# USB_to_UART0_interface.net
KiCad netlist of a schematic drawn in Altium Designer
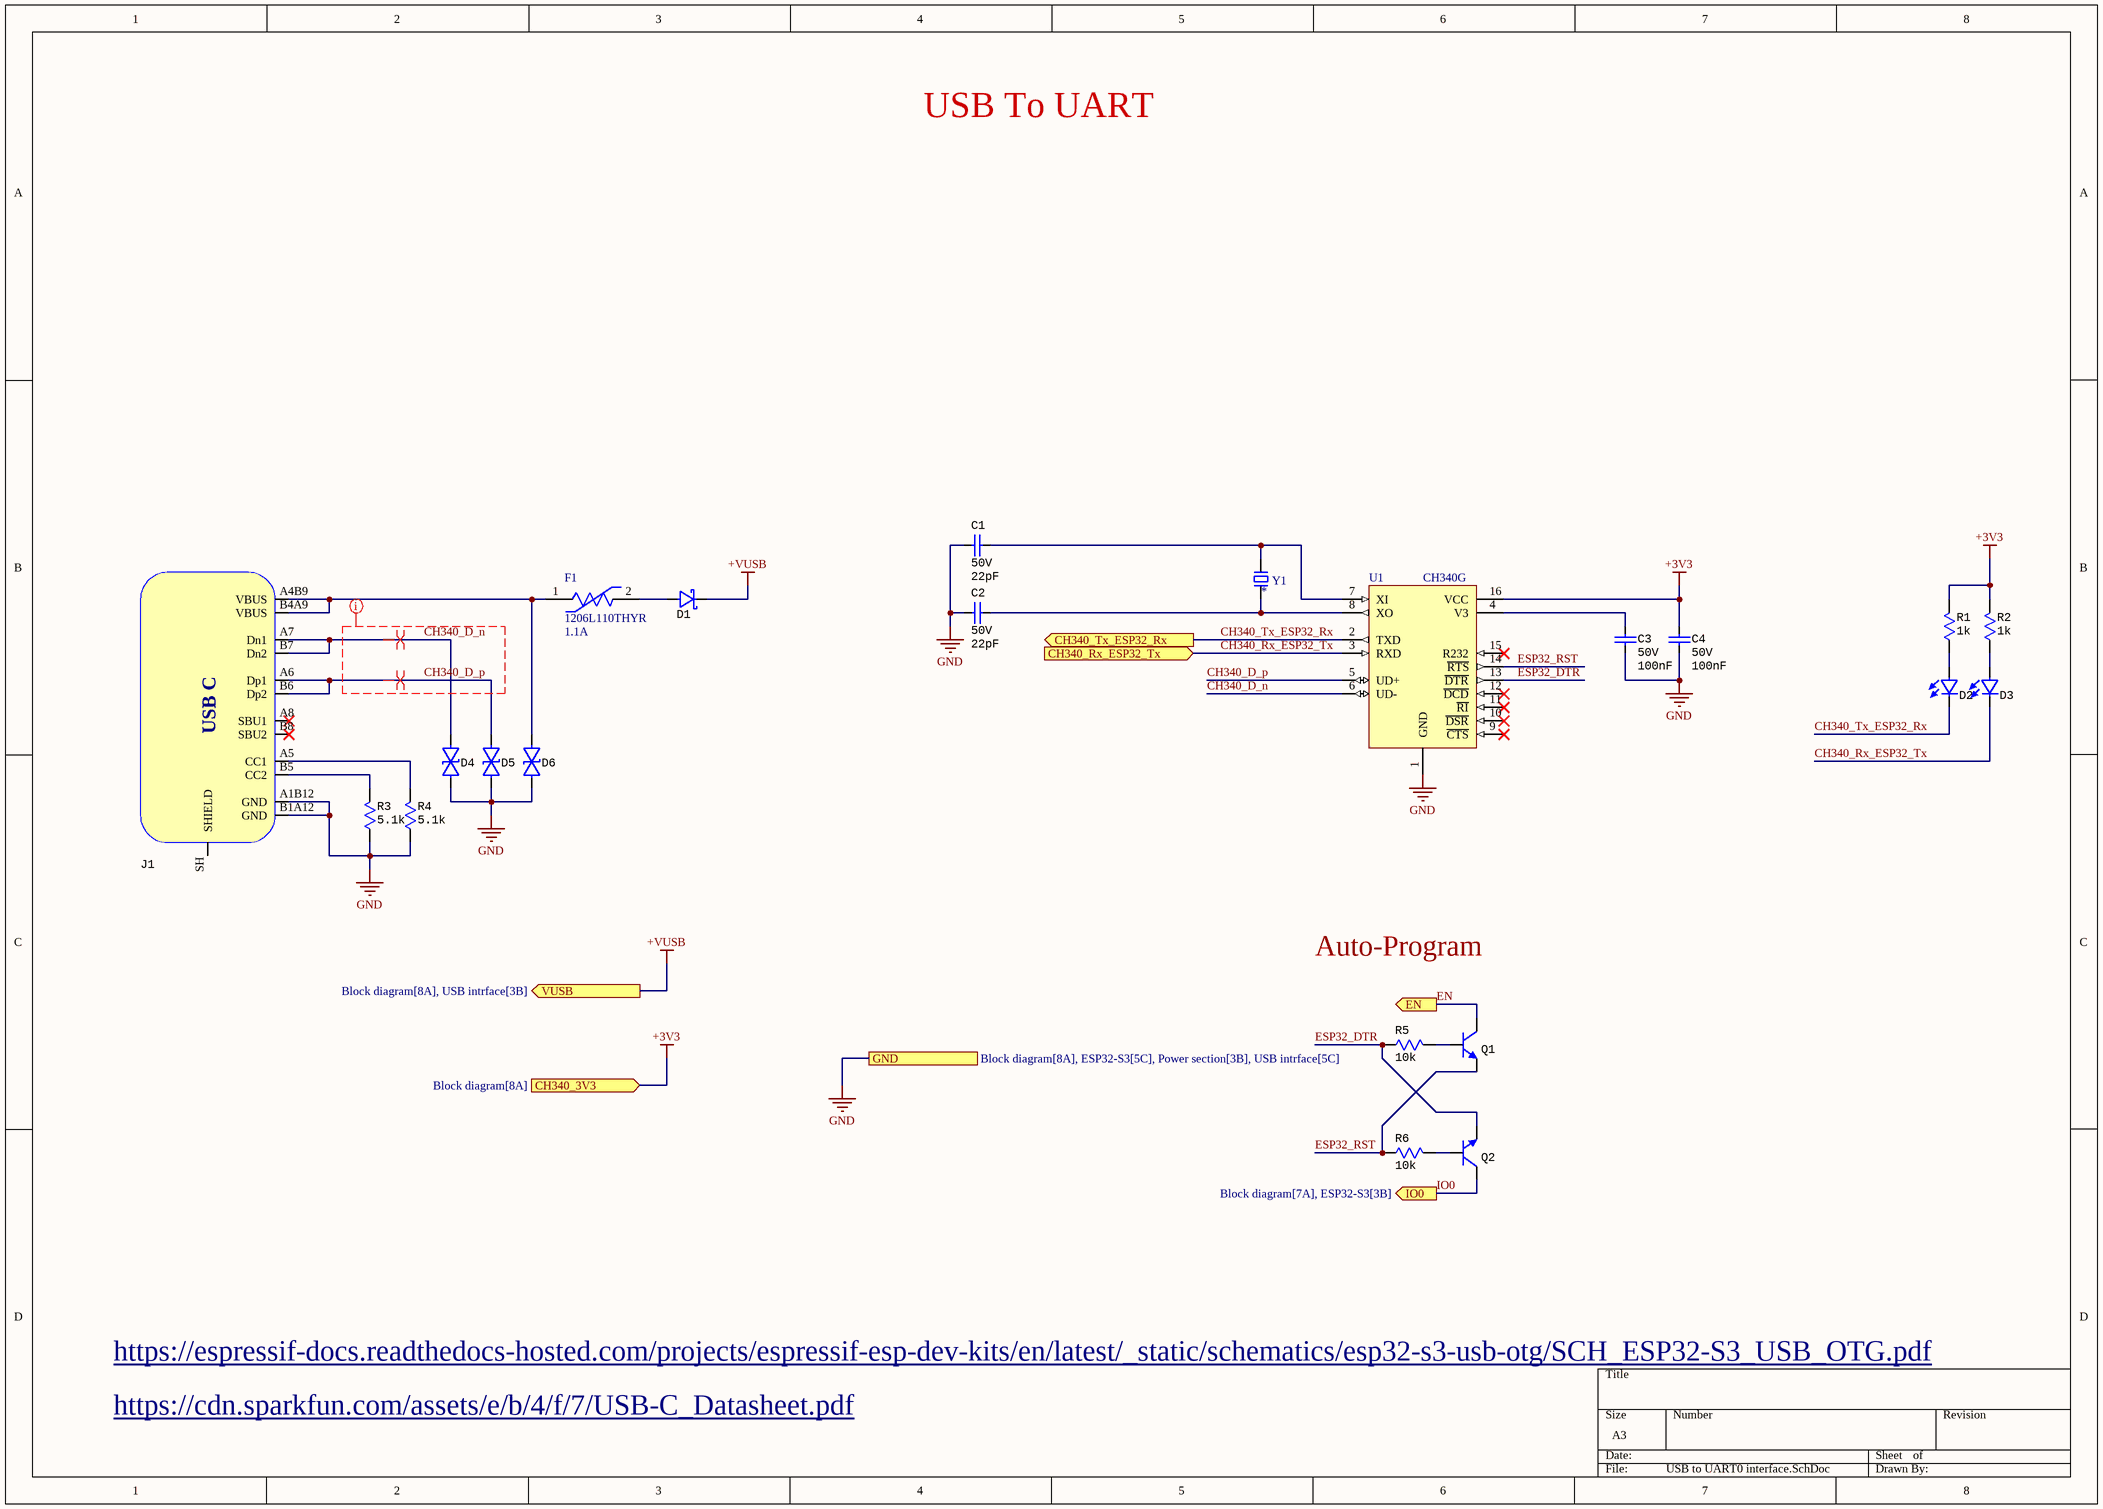
[diagram p0: USB to UART0 interface.SchDoc]

(export (version "E")
  (design (tool "Eeschema 10.0.6"))
  (components
    (comp (ref "C1")
      (value "22pF")
      (footprint "CAP Ceramic SMD 0603")
      (description "CAP CER 22PF 50V C0G/NP0 0603")
      (fields
        (field (name "MANUFACTURER") "Samsung")
        (field (name "MANUFACTURER PART NUMBER") "CL10C220JB81PNC")
        (field (name "VOLTAGE") "50V")
      )
      (libsource (lib "Passive") (part "CAP 0603 22pF 50V"))
    )
    (comp (ref "C2")
      (value "22pF")
      (footprint "CAP Ceramic SMD 0603")
      (description "CAP CER 22PF 50V C0G/NP0 0603")
      (fields
        (field (name "MANUFACTURER") "Samsung")
        (field (name "MANUFACTURER PART NUMBER") "CL10C220JB81PNC")
        (field (name "VOLTAGE") "50V")
      )
      (libsource (lib "Passive") (part "CAP 0603 22pF 50V"))
    )
    (comp (ref "C3")
      (value "100nF")
      (footprint "CAP Ceramic SMD 0603")
      (description "Multilayer Ceramic Capacitors MLCC Surface Mount 0603 0.1uF 50 Volts X7R 10%")
      (fields
        (field (name "MANUFACTURER") "Murata")
        (field (name "MANUFACTURER PART NUMBER") "GRM188R71H104KA93D")
        (field (name "VOLTAGE") "50V")
      )
      (libsource (lib "Passive") (part "CAP 0603 100nF 50V"))
    )
    (comp (ref "C4")
      (value "100nF")
      (footprint "CAP Ceramic SMD 0603")
      (description "Multilayer Ceramic Capacitors MLCC Surface Mount 0603 0.1uF 50 Volts X7R 10%")
      (fields
        (field (name "MANUFACTURER") "Murata")
        (field (name "MANUFACTURER PART NUMBER") "GRM188R71H104KA93D")
        (field (name "VOLTAGE") "50V")
      )
      (libsource (lib "Passive") (part "CAP 0603 100nF 50V"))
    )
    (comp (ref "D1")
      (value "~")
      (footprint "Diode Single SMD SOD123")
      (description "40V 600mV@1A 1A SOD-123 Schottky Barrier Diodes (SBD) ROHS")
      (fields (field (name "MANUFACTURER") "MCC") (field (name "MANUFACTURER PART NUMBER") "B5819W-TP"))
      (libsource (lib "diode") (part "B5819W"))
    )
    (comp (ref "D2")
      (value "~")
      (footprint "LED SMD 0805G")
      (fields
        (field (name "MANUFACTURER") "FOSHAN Nationstar Optoelectronics")
        (field (name "MANUFACTURER PART NUMBER") "NCD0805G1")
      )
      (libsource (lib "diode") (part "LED 0805 Emerald"))
    )
    (comp (ref "D3")
      (value "~")
      (footprint "LED SMD 0805G")
      (fields
        (field (name "MANUFACTURER") "FOSHAN Nationstar Optoelectronics")
        (field (name "MANUFACTURER PART NUMBER") "NCD0805G1")
      )
      (libsource (lib "diode") (part "LED 0805 Emerald"))
    )
    (comp (ref "D4")
      (value "~")
      (footprint "Diode Single SMD SOD523")
      (description "Bi-Directional 9.4A 5V 18.6V 5.6V SOD-523 ESD Protection Devices ROHS")
      (fields
        (field (name "MANUFACTURER") "UMW(Youtai Semiconductor)")
        (field (name "MANUFACTURER PART NUMBER") "LESD5D5.0CT1G")
      )
      (libsource (lib "diode") (part "LESD5D5.0CT1G"))
    )
    (comp (ref "D5")
      (value "~")
      (footprint "Diode Single SMD SOD523")
      (description "Bi-Directional 9.4A 5V 18.6V 5.6V SOD-523 ESD Protection Devices ROHS")
      (fields
        (field (name "MANUFACTURER") "UMW(Youtai Semiconductor)")
        (field (name "MANUFACTURER PART NUMBER") "LESD5D5.0CT1G")
      )
      (libsource (lib "diode") (part "LESD5D5.0CT1G"))
    )
    (comp (ref "D6")
      (value "~")
      (footprint "Diode Single SMD SOD523")
      (description "Bi-Directional 9.4A 5V 18.6V 5.6V SOD-523 ESD Protection Devices ROHS")
      (fields
        (field (name "MANUFACTURER") "UMW(Youtai Semiconductor)")
        (field (name "MANUFACTURER PART NUMBER") "LESD5D5.0CT1G")
      )
      (libsource (lib "diode") (part "LESD5D5.0CT1G"))
    )
    (comp (ref "F1")
      (value "1206L110THYR")
      (footprint "FUSE-1206")
      (description "PTC RESET FUSE 8V 1.1A 1206")
      (fields
        (field (name "MANUFACTURER") "Littelfuse")
        (field (name "OCTOPART") "https://octopart.com/1206l110thyr-littelfuse-11800142")
        (field (name "HOLD CURRENT") "1.1A")
      )
      (libsource (lib "Fuse") (part "1206L110THYR"))
    )
    (comp (ref "J1")
      (value "Connector_USB_Type_C_12Pin")
      (footprint "USB-C-31-M-12 (12PIN)")
      (description "Korean Hroparts Elec\r\nUSB-Type-C\r\nNum of contacts 16\r\nSurface Mount")
      (fields
        (field (name "MANUFACTURER") "Korean Hroparts")
        (field (name "MANUFACTURERPARTNUMBER") "TYPE-C-31-M-12")
      )
      (libsource (lib "USB connectors") (part "Connector_USB_Type_C_12Pin"))
    )
    (comp (ref "Q1")
      (value "~")
      (footprint "SOT23")
      (description "NPN Ic=500mA Vceo=45V hfe=100~250 P=225mW SOT-23")
      (fields
        (field (name "MANUFACTURER") "ON Semiconductor")
        (field (name "MANUFACTURER PART NUMBER") "BC817-16LT1G")
      )
      (libsource (lib "Miscellaneous Transistor") (part "BC817"))
    )
    (comp (ref "Q2")
      (value "~")
      (footprint "SOT23")
      (description "NPN Ic=500mA Vceo=45V hfe=100~250 P=225mW SOT-23")
      (fields
        (field (name "MANUFACTURER") "ON Semiconductor")
        (field (name "MANUFACTURER PART NUMBER") "BC817-16LT1G")
      )
      (libsource (lib "Miscellaneous Transistor") (part "BC817"))
    )
    (comp (ref "R1")
      (value "1k")
      (footprint "RES SMD 0603")
      (description "Res Thick Film 0603 1K Ohm 1% 1/10W ±100ppm/°C Molded SMD Punched Carrier T/R")
      (fields
        (field (name "MANUFACTURER") "Panasonic")
        (field (name "MANUFACTURER PART NUMBER") "ERJ3EKF1001V")
      )
      (libsource (lib "Passive") (part "RES 0603 1k 1%"))
    )
    (comp (ref "R2")
      (value "1k")
      (footprint "RES SMD 0603")
      (description "Res Thick Film 0603 1K Ohm 1% 1/10W ±100ppm/°C Molded SMD Punched Carrier T/R")
      (fields
        (field (name "MANUFACTURER") "Panasonic")
        (field (name "MANUFACTURER PART NUMBER") "ERJ3EKF1001V")
      )
      (libsource (lib "Passive") (part "RES 0603 1k 1%"))
    )
    (comp (ref "R3")
      (value "5.1k")
      (footprint "RES SMD 0603")
      (description "Res Thick Film 0603 5.1K Ohm 1% 1/10W ±100ppm/°C Molded SMD SMD Paper T/R")
      (fields
        (field (name "MANUFACTURER") "Vishay")
        (field (name "MANUFACTURER PART NUMBER") "CRCW06035K10FKEA")
      )
      (libsource (lib "Passive") (part "RES 0603 5.1k 1%"))
    )
    (comp (ref "R4")
      (value "5.1k")
      (footprint "RES SMD 0603")
      (description "Res Thick Film 0603 5.1K Ohm 1% 1/10W ±100ppm/°C Molded SMD SMD Paper T/R")
      (fields
        (field (name "MANUFACTURER") "Vishay")
        (field (name "MANUFACTURER PART NUMBER") "CRCW06035K10FKEA")
      )
      (libsource (lib "Passive") (part "RES 0603 5.1k 1%"))
    )
    (comp (ref "R5")
      (value "10k")
      (footprint "RES SMD 0603")
      (description "Res Thick Film 0603 10K Ohm 1% 1/10W ±100ppm/°C Molded SMD Punched Carrier T/R")
      (fields
        (field (name "MANUFACTURER") "Panasonic")
        (field (name "MANUFACTURER PART NUMBER") "ERJ-3EKF1002V")
      )
      (libsource (lib "Passive") (part "RES 0603 10k 1%"))
    )
    (comp (ref "R6")
      (value "10k")
      (footprint "RES SMD 0603")
      (description "Res Thick Film 0603 10K Ohm 1% 1/10W ±100ppm/°C Molded SMD Punched Carrier T/R")
      (fields
        (field (name "MANUFACTURER") "Panasonic")
        (field (name "MANUFACTURER PART NUMBER") "ERJ-3EKF1002V")
      )
      (libsource (lib "Passive") (part "RES 0603 10k 1%"))
    )
    (comp (ref "U1")
      (value "CH340G")
      (footprint "CH340G")
      (description "Transceiver 2Mbps USB 2.0 SOP-16-150mil USB ICs ROHS")
      (fields (field (name "MANUFACTURER") "WCH(Jiangsu Qin Heng)"))
      (libsource (lib "Communictation ICs") (part "CH340G"))
    )
    (comp (ref "Y1")
      (value "X49SD8MSD2SC")
      (footprint "Crystal TH 2-PIN HC-49S")
      (description "8MHz 49S Crystals 20pF ±20ppm ±30ppm -20℃~+70℃ HC-49S Crystals ROHS")
      (fields (field (name "ALTIUM_VALUE") "*"))
      (libsource (lib "Crystal") (part "X49SD8MSD2SC"))
    )
  )
  (nets
    (net (code "1") (name "+3V3") (class "Default")
      (node (ref "C4") (pin "1") (pinfunction "1_1") (pintype "passive"))
      (node (ref "R1") (pin "2") (pinfunction "2_2") (pintype "passive"))
      (node (ref "R2") (pin "2") (pinfunction "2_2") (pintype "passive"))
      (node (ref "U1") (pin "16") (pinfunction "VCC_16") (pintype "power_in"))
    )
    (net (code "2") (name "+VUSB") (class "Default")
      (node (ref "D1") (pin "2") (pinfunction "2_2") (pintype "passive"))
    )
    (net (code "3") (name "/CH340_D_n") (class "Default")
      (node (ref "D4") (pin "2") (pinfunction "2_2") (pintype "passive"))
      (node (ref "J1") (pin "A7") (pinfunction "Dn1_A7") (pintype "passive"))
      (node (ref "J1") (pin "B7") (pinfunction "Dn2_B7") (pintype "passive"))
      (node (ref "U1") (pin "6") (pinfunction "UD-_6") (pintype "bidirectional"))
    )
    (net (code "4") (name "/CH340_D_p") (class "Default")
      (node (ref "D5") (pin "2") (pinfunction "2_2") (pintype "passive"))
      (node (ref "J1") (pin "A6") (pinfunction "Dp1_A6") (pintype "passive"))
      (node (ref "J1") (pin "B6") (pinfunction "Dp2_B6") (pintype "passive"))
      (node (ref "U1") (pin "5") (pinfunction "UD+_5") (pintype "bidirectional"))
    )
    (net (code "5") (name "/CH340_Rx_ESP32_Tx") (class "Default")
      (node (ref "D3") (pin "2") (pinfunction "2_2") (pintype "passive"))
      (node (ref "U1") (pin "3") (pinfunction "RXD_3") (pintype "input"))
    )
    (net (code "6") (name "/CH340_Tx_ESP32_Rx") (class "Default")
      (node (ref "D2") (pin "2") (pinfunction "2_2") (pintype "passive"))
      (node (ref "U1") (pin "2") (pinfunction "TXD_2") (pintype "output"))
    )
    (net (code "7") (name "/EN") (class "Default")
      (node (ref "Q1") (pin "3") (pinfunction "C_3") (pintype "passive"))
    )
    (net (code "8") (name "/ESP32_DTR") (class "Default")
      (node (ref "Q2") (pin "2") (pinfunction "E_2") (pintype "passive"))
      (node (ref "R5") (pin "1") (pinfunction "1_1") (pintype "passive"))
      (node (ref "U1") (pin "13") (pinfunction "~{DTR}_13") (pintype "output"))
    )
    (net (code "9") (name "/ESP32_RST") (class "Default")
      (node (ref "Q1") (pin "2") (pinfunction "E_2") (pintype "passive"))
      (node (ref "R6") (pin "1") (pinfunction "1_1") (pintype "passive"))
      (node (ref "U1") (pin "14") (pinfunction "~{RTS}_14") (pintype "output"))
    )
    (net (code "10") (name "/IO0") (class "Default")
      (node (ref "Q2") (pin "3") (pinfunction "C_3") (pintype "passive"))
    )
    (net (code "11") (name "GND") (class "Default")
      (node (ref "C1") (pin "1") (pinfunction "1_1") (pintype "passive"))
      (node (ref "C2") (pin "2") (pinfunction "2_2") (pintype "passive"))
      (node (ref "C3") (pin "2") (pinfunction "2_2") (pintype "passive"))
      (node (ref "C4") (pin "2") (pinfunction "2_2") (pintype "passive"))
      (node (ref "D4") (pin "1") (pinfunction "1_1") (pintype "passive"))
      (node (ref "D5") (pin "1") (pinfunction "1_1") (pintype "passive"))
      (node (ref "D6") (pin "1") (pinfunction "1_1") (pintype "passive"))
      (node (ref "J1") (pin "A1B12") (pinfunction "GND_A1B12") (pintype "passive"))
      (node (ref "J1") (pin "B1A12") (pinfunction "GND_B1A12") (pintype "passive"))
      (node (ref "R3") (pin "1") (pinfunction "1_1") (pintype "passive"))
      (node (ref "R4") (pin "1") (pinfunction "1_1") (pintype "passive"))
      (node (ref "U1") (pin "1") (pinfunction "GND_1") (pintype "power_in"))
    )
    (net (code "12") (name "Net-(D1-Pad1)") (class "Default")
      (node (ref "D1") (pin "1") (pinfunction "1_1") (pintype "passive"))
      (node (ref "F1") (pin "2") (pinfunction "2_2") (pintype "passive"))
    )
    (net (code "13") (name "Net-(D2-Pad1)") (class "Default")
      (node (ref "D2") (pin "1") (pinfunction "1_1") (pintype "passive"))
      (node (ref "R1") (pin "1") (pinfunction "1_1") (pintype "passive"))
    )
    (net (code "14") (name "Net-(D3-Pad1)") (class "Default")
      (node (ref "D3") (pin "1") (pinfunction "1_1") (pintype "passive"))
      (node (ref "R2") (pin "1") (pinfunction "1_1") (pintype "passive"))
    )
    (net (code "15") (name "Net-(D6-Pad2)") (class "Default")
      (node (ref "D6") (pin "2") (pinfunction "2_2") (pintype "passive"))
      (node (ref "F1") (pin "1") (pinfunction "1_1") (pintype "passive"))
      (node (ref "J1") (pin "A4B9") (pinfunction "VBUS_A4B9") (pintype "passive"))
      (node (ref "J1") (pin "B4A9") (pinfunction "VBUS_B4A9") (pintype "passive"))
    )
    (net (code "16") (name "Net-(J1-CC1)") (class "Default")
      (node (ref "J1") (pin "A5") (pinfunction "CC1_A5") (pintype "passive"))
      (node (ref "R4") (pin "2") (pinfunction "2_2") (pintype "passive"))
    )
    (net (code "17") (name "Net-(J1-CC2)") (class "Default")
      (node (ref "J1") (pin "B5") (pinfunction "CC2_B5") (pintype "passive"))
      (node (ref "R3") (pin "2") (pinfunction "2_2") (pintype "passive"))
    )
    (net (code "18") (name "Net-(Q1-B)") (class "Default")
      (node (ref "Q1") (pin "1") (pinfunction "B_1") (pintype "passive"))
      (node (ref "R5") (pin "2") (pinfunction "2_2") (pintype "passive"))
    )
    (net (code "19") (name "Net-(Q2-B)") (class "Default")
      (node (ref "Q2") (pin "1") (pinfunction "B_1") (pintype "passive"))
      (node (ref "R6") (pin "2") (pinfunction "2_2") (pintype "passive"))
    )
    (net (code "20") (name "Net-(U1-V3)") (class "Default")
      (node (ref "C3") (pin "1") (pinfunction "1_1") (pintype "passive"))
      (node (ref "U1") (pin "4") (pinfunction "V3_4") (pintype "power_in"))
    )
    (net (code "21") (name "Net-(U1-XI)") (class "Default")
      (node (ref "C1") (pin "2") (pinfunction "2_2") (pintype "passive"))
      (node (ref "U1") (pin "7") (pinfunction "XI_7") (pintype "input"))
      (node (ref "Y1") (pin "1") (pinfunction "1_1") (pintype "passive"))
    )
    (net (code "22") (name "Net-(U1-XO)") (class "Default")
      (node (ref "C2") (pin "1") (pinfunction "1_1") (pintype "passive"))
      (node (ref "U1") (pin "8") (pinfunction "XO_8") (pintype "output"))
      (node (ref "Y1") (pin "2") (pinfunction "2_2") (pintype "passive"))
    )
    (net (code "23") (name "unconnected-(J1-SBU1-PadA8)") (class "Default")
      (node (ref "J1") (pin "A8") (pinfunction "SBU1_A8") (pintype "passive+no_connect"))
    )
    (net (code "24") (name "unconnected-(J1-SBU2-PadB8)") (class "Default")
      (node (ref "J1") (pin "B8") (pinfunction "SBU2_B8") (pintype "passive+no_connect"))
    )
    (net (code "25") (name "unconnected-(J1-SHIELD-PadSH)") (class "Default")
      (node (ref "J1") (pin "SH") (pinfunction "SHIELD_SH") (pintype "passive"))
    )
    (net (code "26") (name "unconnected-(U1-R232-Pad15)") (class "Default")
      (node (ref "U1") (pin "15") (pinfunction "R232_15") (pintype "input+no_connect"))
    )
    (net (code "27") (name "unconnected-(U1-~{CTS}-Pad9)") (class "Default")
      (node (ref "U1") (pin "9") (pinfunction "~{CTS}_9") (pintype "input+no_connect"))
    )
    (net (code "28") (name "unconnected-(U1-~{DCD}-Pad12)") (class "Default")
      (node (ref "U1") (pin "12") (pinfunction "~{DCD}_12") (pintype "input+no_connect"))
    )
    (net (code "29") (name "unconnected-(U1-~{DSR}-Pad10)") (class "Default")
      (node (ref "U1") (pin "10") (pinfunction "~{DSR}_10") (pintype "input+no_connect"))
    )
    (net (code "30") (name "unconnected-(U1-~{RI}-Pad11)") (class "Default")
      (node (ref "U1") (pin "11") (pinfunction "~{RI}_11") (pintype "input+no_connect"))
    )
  )
)
